# M7010X.net
KiCad netlist of a schematic drawn in EAGLE
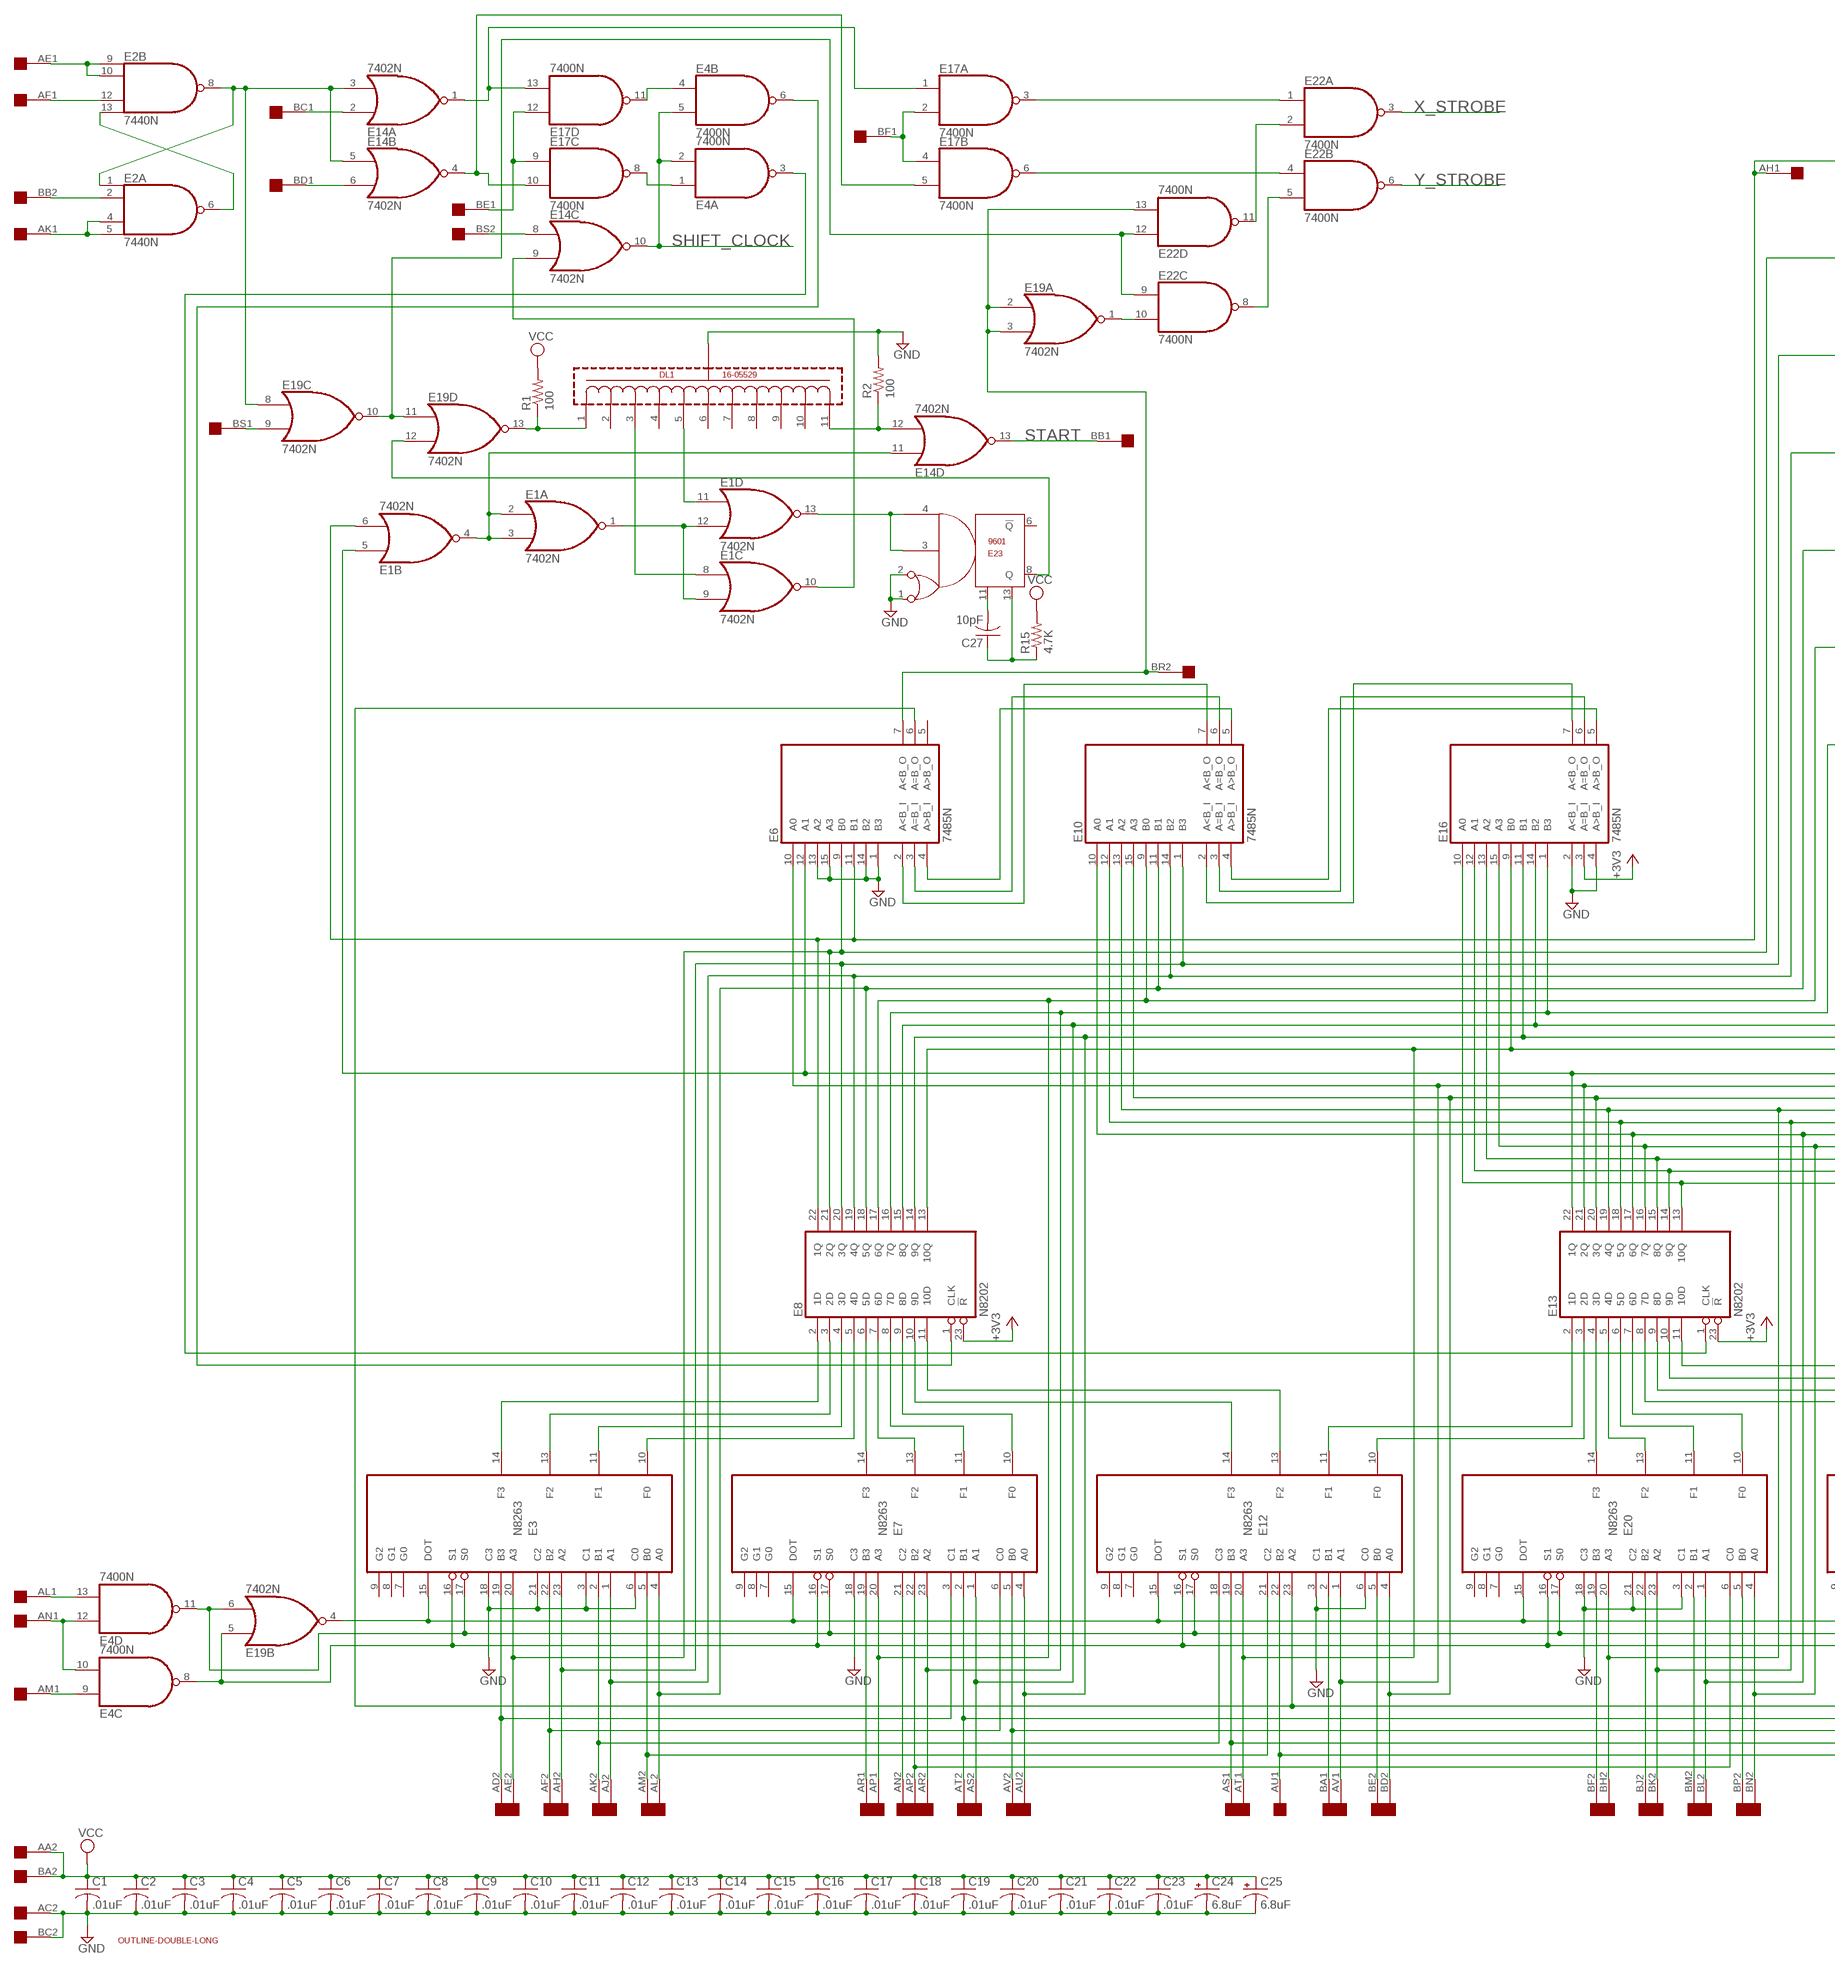
[diagram p0: schematic, sheet 1, part 1 of 2]
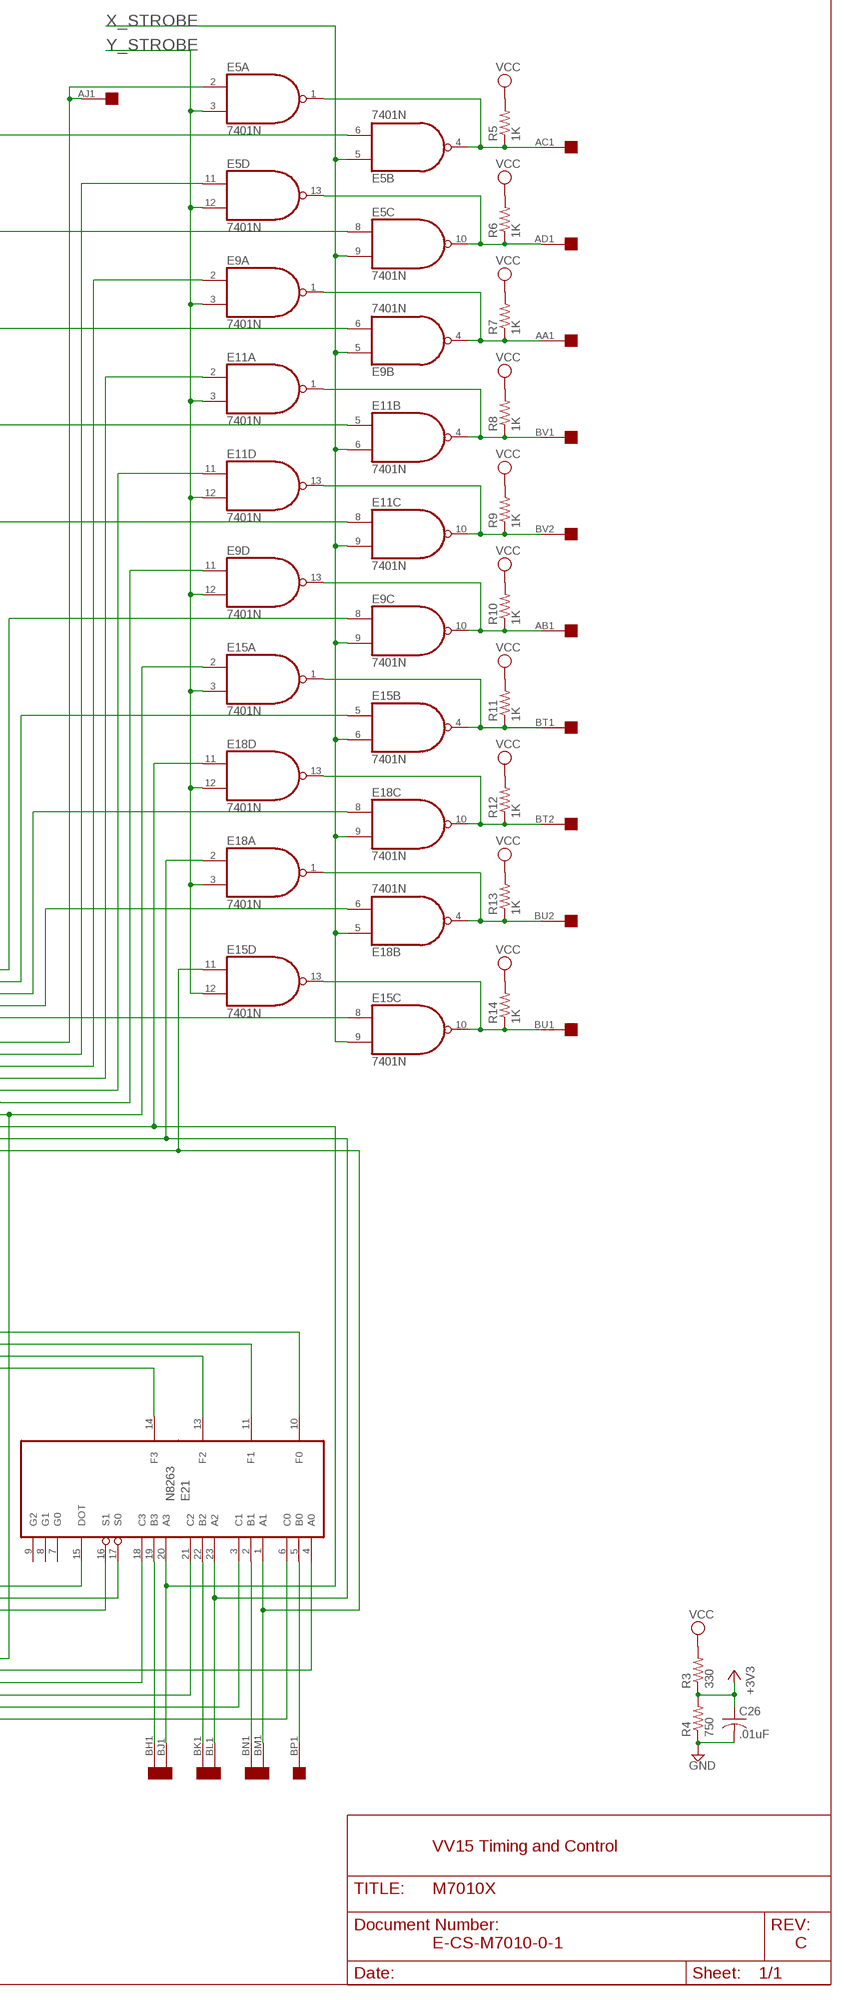
[diagram p1: schematic, sheet 1, part 2 of 2]

(export (version "E")
  (design (tool "Eeschema 10.0.6"))
  (components
    (comp (ref "C1")
      (value ".01uF")
      (footprint "eagle-import:C050-025X075")
      (libsource (lib "eagle-import") (part "C-US050-025X075"))
    )
    (comp (ref "C2")
      (value ".01uF")
      (footprint "eagle-import:C050-025X075")
      (libsource (lib "eagle-import") (part "C-US050-025X075"))
    )
    (comp (ref "C3")
      (value ".01uF")
      (footprint "eagle-import:C050-025X075")
      (libsource (lib "eagle-import") (part "C-US050-025X075"))
    )
    (comp (ref "C4")
      (value ".01uF")
      (footprint "eagle-import:C050-025X075")
      (libsource (lib "eagle-import") (part "C-US050-025X075"))
    )
    (comp (ref "C5")
      (value ".01uF")
      (footprint "eagle-import:C050-025X075")
      (libsource (lib "eagle-import") (part "C-US050-025X075"))
    )
    (comp (ref "C6")
      (value ".01uF")
      (footprint "eagle-import:C050-025X075")
      (libsource (lib "eagle-import") (part "C-US050-025X075"))
    )
    (comp (ref "C7")
      (value ".01uF")
      (footprint "eagle-import:C050-025X075")
      (libsource (lib "eagle-import") (part "C-US050-025X075"))
    )
    (comp (ref "C8")
      (value ".01uF")
      (footprint "eagle-import:C050-025X075")
      (libsource (lib "eagle-import") (part "C-US050-025X075"))
    )
    (comp (ref "C9")
      (value ".01uF")
      (footprint "eagle-import:C050-025X075")
      (libsource (lib "eagle-import") (part "C-US050-025X075"))
    )
    (comp (ref "C10")
      (value ".01uF")
      (footprint "eagle-import:C050-025X075")
      (libsource (lib "eagle-import") (part "C-US050-025X075"))
    )
    (comp (ref "C11")
      (value ".01uF")
      (footprint "eagle-import:C050-025X075")
      (libsource (lib "eagle-import") (part "C-US050-025X075"))
    )
    (comp (ref "C12")
      (value ".01uF")
      (footprint "eagle-import:C050-025X075")
      (libsource (lib "eagle-import") (part "C-US050-025X075"))
    )
    (comp (ref "C13")
      (value ".01uF")
      (footprint "eagle-import:C050-025X075")
      (libsource (lib "eagle-import") (part "C-US050-025X075"))
    )
    (comp (ref "C14")
      (value ".01uF")
      (footprint "eagle-import:C050-025X075")
      (libsource (lib "eagle-import") (part "C-US050-025X075"))
    )
    (comp (ref "C15")
      (value ".01uF")
      (footprint "eagle-import:C050-025X075")
      (libsource (lib "eagle-import") (part "C-US050-025X075"))
    )
    (comp (ref "C16")
      (value ".01uF")
      (footprint "eagle-import:C050-025X075")
      (libsource (lib "eagle-import") (part "C-US050-025X075"))
    )
    (comp (ref "C17")
      (value ".01uF")
      (footprint "eagle-import:C050-025X075")
      (libsource (lib "eagle-import") (part "C-US050-025X075"))
    )
    (comp (ref "C18")
      (value ".01uF")
      (footprint "eagle-import:C050-025X075")
      (libsource (lib "eagle-import") (part "C-US050-025X075"))
    )
    (comp (ref "C19")
      (value ".01uF")
      (footprint "eagle-import:C050-025X075")
      (libsource (lib "eagle-import") (part "C-US050-025X075"))
    )
    (comp (ref "C20")
      (value ".01uF")
      (footprint "eagle-import:C050-025X075")
      (libsource (lib "eagle-import") (part "C-US050-025X075"))
    )
    (comp (ref "C21")
      (value ".01uF")
      (footprint "eagle-import:C050-025X075")
      (libsource (lib "eagle-import") (part "C-US050-025X075"))
    )
    (comp (ref "C22")
      (value ".01uF")
      (footprint "eagle-import:C050-025X075")
      (libsource (lib "eagle-import") (part "C-US050-025X075"))
    )
    (comp (ref "C23")
      (value ".01uF")
      (footprint "eagle-import:C050-025X075")
      (libsource (lib "eagle-import") (part "C-US050-025X075"))
    )
    (comp (ref "C24")
      (value "6.8uF")
      (footprint "eagle-import:E12-8")
      (libsource (lib "eagle-import") (part "CPOL-USE20-8AXIAL"))
    )
    (comp (ref "C25")
      (value "6.8uF")
      (footprint "eagle-import:E12-8")
      (libsource (lib "eagle-import") (part "CPOL-USE20-8AXIAL"))
    )
    (comp (ref "C26")
      (value ".01uF")
      (footprint "eagle-import:C050-025X075")
      (libsource (lib "eagle-import") (part "C-US050-025X075"))
    )
    (comp (ref "C27")
      (value "10pF")
      (footprint "eagle-import:C050-025X075")
      (libsource (lib "eagle-import") (part "C-US050-025X075"))
    )
    (comp (ref "DL1")
      (value "16-05529")
      (footprint "eagle-import:16-05529")
      (libsource (lib "eagle-import") (part "16-05529"))
    )
    (comp (ref "E1")
      (value "7402N")
      (footprint "eagle-import:DIL14")
      (libsource (lib "eagle-import") (part "7402N"))
    )
    (comp (ref "E2")
      (value "7440N")
      (footprint "eagle-import:DIL14")
      (libsource (lib "eagle-import") (part "7420N"))
    )
    (comp (ref "E3")
      (value "N8263")
      (footprint "eagle-import:DIL24")
      (libsource (lib "eagle-import") (part "N8263"))
    )
    (comp (ref "E4")
      (value "7400N")
      (footprint "eagle-import:DIL14")
      (libsource (lib "eagle-import") (part "7400N"))
    )
    (comp (ref "E5")
      (value "7401N")
      (footprint "eagle-import:DIL14")
      (libsource (lib "eagle-import") (part "7401NLS"))
    )
    (comp (ref "E6")
      (value "7485N")
      (footprint "eagle-import:DIL16")
      (libsource (lib "eagle-import") (part "7485N"))
    )
    (comp (ref "E7")
      (value "N8263")
      (footprint "eagle-import:DIL24")
      (libsource (lib "eagle-import") (part "N8263"))
    )
    (comp (ref "E8")
      (value "N8202")
      (footprint "eagle-import:DIL24")
      (libsource (lib "eagle-import") (part "N8202"))
    )
    (comp (ref "E9")
      (value "7401N")
      (footprint "eagle-import:DIL14")
      (libsource (lib "eagle-import") (part "7401NLS"))
    )
    (comp (ref "E10")
      (value "7485N")
      (footprint "eagle-import:DIL16")
      (libsource (lib "eagle-import") (part "7485N"))
    )
    (comp (ref "E11")
      (value "7401N")
      (footprint "eagle-import:DIL14")
      (libsource (lib "eagle-import") (part "7401NLS"))
    )
    (comp (ref "E12")
      (value "N8263")
      (footprint "eagle-import:DIL24")
      (libsource (lib "eagle-import") (part "N8263"))
    )
    (comp (ref "E13")
      (value "N8202")
      (footprint "eagle-import:DIL24")
      (libsource (lib "eagle-import") (part "N8202"))
    )
    (comp (ref "E14")
      (value "7402N")
      (footprint "eagle-import:DIL14")
      (libsource (lib "eagle-import") (part "7402N"))
    )
    (comp (ref "E15")
      (value "7401N")
      (footprint "eagle-import:DIL14")
      (libsource (lib "eagle-import") (part "7401NLS"))
    )
    (comp (ref "E16")
      (value "7485N")
      (footprint "eagle-import:DIL16")
      (libsource (lib "eagle-import") (part "7485N"))
    )
    (comp (ref "E17")
      (value "7400N")
      (footprint "eagle-import:DIL14")
      (libsource (lib "eagle-import") (part "7400N"))
    )
    (comp (ref "E18")
      (value "7401N")
      (footprint "eagle-import:DIL14")
      (libsource (lib "eagle-import") (part "7401NLS"))
    )
    (comp (ref "E19")
      (value "7402N")
      (footprint "eagle-import:DIL14")
      (libsource (lib "eagle-import") (part "7402N"))
    )
    (comp (ref "E20")
      (value "N8263")
      (footprint "eagle-import:DIL24")
      (libsource (lib "eagle-import") (part "N8263"))
    )
    (comp (ref "E21")
      (value "N8263")
      (footprint "eagle-import:DIL24")
      (libsource (lib "eagle-import") (part "N8263"))
    )
    (comp (ref "E22")
      (value "7400N")
      (footprint "eagle-import:DIL14")
      (libsource (lib "eagle-import") (part "7400N"))
    )
    (comp (ref "E23")
      (value "9601")
      (footprint "eagle-import:DIL14")
      (libsource (lib "eagle-import") (part "9601"))
    )
    (comp (ref "R1")
      (value "100")
      (footprint "eagle-import:0207_10")
      (libsource (lib "eagle-import") (part "R-US_0207/10"))
    )
    (comp (ref "R2")
      (value "100")
      (footprint "eagle-import:0207_10")
      (libsource (lib "eagle-import") (part "R-US_0207/10"))
    )
    (comp (ref "R3")
      (value "330")
      (footprint "eagle-import:0207_10")
      (libsource (lib "eagle-import") (part "R-US_0207/10"))
    )
    (comp (ref "R4")
      (value "750")
      (footprint "eagle-import:0207_10")
      (libsource (lib "eagle-import") (part "R-US_0207/10"))
    )
    (comp (ref "R5")
      (value "1K")
      (footprint "eagle-import:0207_10")
      (libsource (lib "eagle-import") (part "R-US_0207/10"))
    )
    (comp (ref "R6")
      (value "1K")
      (footprint "eagle-import:0207_10")
      (libsource (lib "eagle-import") (part "R-US_0207/10"))
    )
    (comp (ref "R7")
      (value "1K")
      (footprint "eagle-import:0207_10")
      (libsource (lib "eagle-import") (part "R-US_0207/10"))
    )
    (comp (ref "R8")
      (value "1K")
      (footprint "eagle-import:0207_10")
      (libsource (lib "eagle-import") (part "R-US_0207/10"))
    )
    (comp (ref "R9")
      (value "1K")
      (footprint "eagle-import:0207_10")
      (libsource (lib "eagle-import") (part "R-US_0207/10"))
    )
    (comp (ref "R10")
      (value "1K")
      (footprint "eagle-import:0207_10")
      (libsource (lib "eagle-import") (part "R-US_0207/10"))
    )
    (comp (ref "R11")
      (value "1K")
      (footprint "eagle-import:0207_10")
      (libsource (lib "eagle-import") (part "R-US_0207/10"))
    )
    (comp (ref "R12")
      (value "1K")
      (footprint "eagle-import:0207_10")
      (libsource (lib "eagle-import") (part "R-US_0207/10"))
    )
    (comp (ref "R13")
      (value "1K")
      (footprint "eagle-import:0207_10")
      (libsource (lib "eagle-import") (part "R-US_0207/10"))
    )
    (comp (ref "R14")
      (value "1K")
      (footprint "eagle-import:0207_10")
      (libsource (lib "eagle-import") (part "R-US_0207/10"))
    )
    (comp (ref "R15")
      (value "4.7K")
      (footprint "eagle-import:0207_10")
      (libsource (lib "eagle-import") (part "R-US_0207/10"))
    )
    (comp (ref "U$1")
      (value "OUTLINE-DOUBLE-LONG")
      (footprint "eagle-import:DOUBLE-LONG")
      (libsource (lib "eagle-import") (part "OUTLINE-DOUBLE-LONG"))
    )
    (comp (ref "U$3")
      (value "DOUBLE")
      (footprint "eagle-import:EDGE-CON4")
      (libsource (lib "eagle-import") (part "DOUBLE"))
    )
  )
  (nets
    (net (code "1") (name "+3V3") (class "Default")
      (node (ref "C26") (pin "1") (pinfunction "1_1") (pintype "passive"))
      (node (ref "E13") (pin "23") (pinfunction "~{R}_23") (pintype "input"))
      (node (ref "E16") (pin "3") (pinfunction "A=B_I_3") (pintype "input"))
      (node (ref "E8") (pin "23") (pinfunction "~{R}_23") (pintype "input"))
      (node (ref "R3") (pin "1") (pinfunction "1_1") (pintype "passive"))
      (node (ref "R4") (pin "2") (pinfunction "2_2") (pintype "passive"))
    )
    (net (code "2") (name "/SHIFT_CLOCK") (class "Default")
      (node (ref "E14") (pin "10") (pinfunction "O_10") (pintype "output"))
      (node (ref "E4") (pin "2") (pinfunction "I1_2") (pintype "input"))
      (node (ref "E4") (pin "5") (pinfunction "I1_5") (pintype "input"))
    )
    (net (code "3") (name "/START") (class "Default")
      (node (ref "E14") (pin "13") (pinfunction "O_13") (pintype "output"))
      (node (ref "U$3") (pin "BB1") (pinfunction "1_BB1") (pintype "bidirectional"))
    )
    (net (code "4") (name "/X_STROBE") (class "Default")
      (node (ref "E11") (pin "6") (pinfunction "I1_6") (pintype "input"))
      (node (ref "E11") (pin "9") (pinfunction "I1_9") (pintype "input"))
      (node (ref "E15") (pin "6") (pinfunction "I1_6") (pintype "input"))
      (node (ref "E15") (pin "9") (pinfunction "I1_9") (pintype "input"))
      (node (ref "E18") (pin "5") (pinfunction "I0_5") (pintype "input"))
      (node (ref "E18") (pin "9") (pinfunction "I1_9") (pintype "input"))
      (node (ref "E22") (pin "3") (pinfunction "O_3") (pintype "output"))
      (node (ref "E5") (pin "5") (pinfunction "I0_5") (pintype "input"))
      (node (ref "E5") (pin "9") (pinfunction "I1_9") (pintype "input"))
      (node (ref "E9") (pin "5") (pinfunction "I0_5") (pintype "input"))
      (node (ref "E9") (pin "9") (pinfunction "I1_9") (pintype "input"))
    )
    (net (code "5") (name "/Y_STROBE") (class "Default")
      (node (ref "E11") (pin "12") (pinfunction "I1_12") (pintype "input"))
      (node (ref "E11") (pin "3") (pinfunction "I1_3") (pintype "input"))
      (node (ref "E15") (pin "12") (pinfunction "I1_12") (pintype "input"))
      (node (ref "E15") (pin "3") (pinfunction "I1_3") (pintype "input"))
      (node (ref "E18") (pin "12") (pinfunction "I1_12") (pintype "input"))
      (node (ref "E18") (pin "3") (pinfunction "I1_3") (pintype "input"))
      (node (ref "E22") (pin "6") (pinfunction "O_6") (pintype "output"))
      (node (ref "E5") (pin "12") (pinfunction "I1_12") (pintype "input"))
      (node (ref "E5") (pin "3") (pinfunction "I1_3") (pintype "input"))
      (node (ref "E9") (pin "12") (pinfunction "I1_12") (pintype "input"))
      (node (ref "E9") (pin "3") (pinfunction "I1_3") (pintype "input"))
    )
    (net (code "6") (name "GND") (class "Default")
      (node (ref "C1") (pin "2") (pinfunction "2_2") (pintype "passive"))
      (node (ref "C10") (pin "2") (pinfunction "2_2") (pintype "passive"))
      (node (ref "C11") (pin "2") (pinfunction "2_2") (pintype "passive"))
      (node (ref "C12") (pin "2") (pinfunction "2_2") (pintype "passive"))
      (node (ref "C13") (pin "2") (pinfunction "2_2") (pintype "passive"))
      (node (ref "C14") (pin "2") (pinfunction "2_2") (pintype "passive"))
      (node (ref "C15") (pin "2") (pinfunction "2_2") (pintype "passive"))
      (node (ref "C16") (pin "2") (pinfunction "2_2") (pintype "passive"))
      (node (ref "C17") (pin "2") (pinfunction "2_2") (pintype "passive"))
      (node (ref "C18") (pin "2") (pinfunction "2_2") (pintype "passive"))
      (node (ref "C19") (pin "2") (pinfunction "2_2") (pintype "passive"))
      (node (ref "C2") (pin "2") (pinfunction "2_2") (pintype "passive"))
      (node (ref "C20") (pin "2") (pinfunction "2_2") (pintype "passive"))
      (node (ref "C21") (pin "2") (pinfunction "2_2") (pintype "passive"))
      (node (ref "C22") (pin "2") (pinfunction "2_2") (pintype "passive"))
      (node (ref "C23") (pin "2") (pinfunction "2_2") (pintype "passive"))
      (node (ref "C24") (pin "-") (pinfunction "-_-") (pintype "passive"))
      (node (ref "C25") (pin "-") (pinfunction "-_-") (pintype "passive"))
      (node (ref "C26") (pin "2") (pinfunction "2_2") (pintype "passive"))
      (node (ref "C3") (pin "2") (pinfunction "2_2") (pintype "passive"))
      (node (ref "C4") (pin "2") (pinfunction "2_2") (pintype "passive"))
      (node (ref "C5") (pin "2") (pinfunction "2_2") (pintype "passive"))
      (node (ref "C6") (pin "2") (pinfunction "2_2") (pintype "passive"))
      (node (ref "C7") (pin "2") (pinfunction "2_2") (pintype "passive"))
      (node (ref "C8") (pin "2") (pinfunction "2_2") (pintype "passive"))
      (node (ref "C9") (pin "2") (pinfunction "2_2") (pintype "passive"))
      (node (ref "DL1") (pin "12") (pinfunction "GND_12") (pintype "passive"))
      (node (ref "E12") (pin "3") (pinfunction "C1_3") (pintype "input"))
      (node (ref "E12") (pin "6") (pinfunction "C0_6") (pintype "input"))
      (node (ref "E16") (pin "2") (pinfunction "A<B_I_2") (pintype "input"))
      (node (ref "E16") (pin "4") (pinfunction "A>B_I_4") (pintype "input"))
      (node (ref "E20") (pin "18") (pinfunction "C3_18") (pintype "input"))
      (node (ref "E20") (pin "21") (pinfunction "C2_21") (pintype "input"))
      (node (ref "E20") (pin "3") (pinfunction "C1_3") (pintype "input"))
      (node (ref "E23") (pin "1") (pinfunction "P$1_1") (pintype "input"))
      (node (ref "E23") (pin "2") (pinfunction "P$2_2") (pintype "input"))
      (node (ref "E3") (pin "18") (pinfunction "C3_18") (pintype "input"))
      (node (ref "E3") (pin "21") (pinfunction "C2_21") (pintype "input"))
      (node (ref "E3") (pin "3") (pinfunction "C1_3") (pintype "input"))
      (node (ref "E3") (pin "6") (pinfunction "C0_6") (pintype "input"))
      (node (ref "E6") (pin "1") (pinfunction "B3_1") (pintype "input"))
      (node (ref "E6") (pin "13") (pinfunction "A2_13") (pintype "input"))
      (node (ref "E6") (pin "14") (pinfunction "B2_14") (pintype "input"))
      (node (ref "E6") (pin "15") (pinfunction "A3_15") (pintype "input"))
      (node (ref "E7") (pin "18") (pinfunction "C3_18") (pintype "input"))
      (node (ref "R2") (pin "2") (pinfunction "2_2") (pintype "passive"))
      (node (ref "R4") (pin "1") (pinfunction "1_1") (pintype "passive"))
      (node (ref "U$3") (pin "AC2") (pinfunction "1_AC2") (pintype "bidirectional"))
      (node (ref "U$3") (pin "BC2") (pinfunction "1_BC2") (pintype "bidirectional"))
    )
    (net (code "7") (name "Net-(DL1-0)") (class "Default")
      (node (ref "DL1") (pin "1") (pinfunction "0_1") (pintype "passive"))
      (node (ref "E19") (pin "13") (pinfunction "O_13") (pintype "output"))
      (node (ref "R1") (pin "1") (pinfunction "1_1") (pintype "passive"))
    )
    (net (code "8") (name "Net-(DL1-10)") (class "Default")
      (node (ref "DL1") (pin "3") (pinfunction "10_3") (pintype "passive"))
      (node (ref "E1") (pin "8") (pinfunction "I0_8") (pintype "input"))
    )
    (net (code "9") (name "Net-(DL1-20)") (class "Default")
      (node (ref "DL1") (pin "5") (pinfunction "20_5") (pintype "passive"))
      (node (ref "E1") (pin "11") (pinfunction "I0_11") (pintype "input"))
    )
    (net (code "10") (name "Net-(DL1-50)") (class "Default")
      (node (ref "DL1") (pin "11") (pinfunction "50_11") (pintype "passive"))
      (node (ref "E14") (pin "12") (pinfunction "I1_12") (pintype "input"))
      (node (ref "R2") (pin "1") (pinfunction "1_1") (pintype "passive"))
    )
    (net (code "11") (name "Net-(E1A-O)") (class "Default")
      (node (ref "E1") (pin "1") (pinfunction "O_1") (pintype "output"))
      (node (ref "E1") (pin "12") (pinfunction "I1_12") (pintype "input"))
      (node (ref "E1") (pin "9") (pinfunction "I1_9") (pintype "input"))
    )
    (net (code "12") (name "Net-(E1B-I1)") (class "Default")
      (node (ref "E1") (pin "6") (pinfunction "I1_6") (pintype "input"))
      (node (ref "E5") (pin "6") (pinfunction "I1_6") (pintype "input"))
      (node (ref "E6") (pin "11") (pinfunction "B1_11") (pintype "input"))
      (node (ref "E8") (pin "22") (pinfunction "1Q_22") (pintype "tri_state"))
      (node (ref "U$3") (pin "AH1") (pinfunction "1_AH1") (pintype "bidirectional"))
    )
    (net (code "13") (name "Net-(E1D-O)") (class "Default")
      (node (ref "E1") (pin "13") (pinfunction "O_13") (pintype "output"))
      (node (ref "E23") (pin "3") (pinfunction "P$3_3") (pintype "input"))
      (node (ref "E23") (pin "4") (pinfunction "P$4_4") (pintype "input"))
    )
    (net (code "14") (name "Net-(E2C-I1)") (class "Default")
      (node (ref "E2") (pin "2") (pinfunction "I1_2") (pintype "input"))
      (node (ref "U$3") (pin "BB2") (pinfunction "1_BB2") (pintype "bidirectional"))
    )
    (net (code "15") (name "Net-(E2C-I2)") (class "Default")
      (node (ref "E2") (pin "4") (pinfunction "I2_4") (pintype "input"))
      (node (ref "E2") (pin "5") (pinfunction "I3_5") (pintype "input"))
      (node (ref "U$3") (pin "AK1") (pinfunction "1_AK1") (pintype "bidirectional"))
    )
    (net (code "16") (name "Net-(E2C-O)") (class "Default")
      (node (ref "E2") (pin "13") (pinfunction "I3_13") (pintype "input"))
      (node (ref "E2") (pin "6") (pinfunction "O_6") (pintype "output"))
    )
    (net (code "17") (name "Net-(E2D-I0)") (class "Default")
      (node (ref "E2") (pin "10") (pinfunction "I1_10") (pintype "input"))
      (node (ref "E2") (pin "9") (pinfunction "I0_9") (pintype "input"))
      (node (ref "U$3") (pin "AE1") (pinfunction "1_AE1") (pintype "bidirectional"))
    )
    (net (code "18") (name "Net-(E2D-I2)") (class "Default")
      (node (ref "E2") (pin "12") (pinfunction "I2_12") (pintype "input"))
      (node (ref "U$3") (pin "AF1") (pinfunction "1_AF1") (pintype "bidirectional"))
    )
    (net (code "19") (name "Net-(E3A-A3)") (class "Default")
      (node (ref "E3") (pin "20") (pinfunction "A3_20") (pintype "input"))
      (node (ref "E5") (pin "8") (pinfunction "I0_8") (pintype "input"))
      (node (ref "E6") (pin "9") (pinfunction "B0_9") (pintype "input"))
      (node (ref "E8") (pin "21") (pinfunction "2Q_21") (pintype "tri_state"))
      (node (ref "U$3") (pin "AE2") (pinfunction "1_AE2") (pintype "bidirectional"))
    )
    (net (code "20") (name "Net-(E3A-B2)") (class "Default")
      (node (ref "E3") (pin "22") (pinfunction "B2_22") (pintype "input"))
      (node (ref "E7") (pin "6") (pinfunction "C0_6") (pintype "input"))
      (node (ref "U$3") (pin "AF2") (pinfunction "1_AF2") (pintype "bidirectional"))
    )
    (net (code "21") (name "Net-(E3A-B3)") (class "Default")
      (node (ref "E3") (pin "19") (pinfunction "B3_19") (pintype "input"))
      (node (ref "E7") (pin "3") (pinfunction "C1_3") (pintype "input"))
      (node (ref "U$3") (pin "AD2") (pinfunction "1_AD2") (pintype "bidirectional"))
    )
    (net (code "22") (name "Net-(E3A-F0)") (class "Default")
      (node (ref "E3") (pin "10") (pinfunction "F0_10") (pintype "output"))
      (node (ref "E8") (pin "5") (pinfunction "4D_5") (pintype "input"))
    )
    (net (code "23") (name "Net-(E3A-F1)") (class "Default")
      (node (ref "E3") (pin "11") (pinfunction "F1_11") (pintype "output"))
      (node (ref "E8") (pin "4") (pinfunction "3D_4") (pintype "input"))
    )
    (net (code "24") (name "Net-(E3A-F2)") (class "Default")
      (node (ref "E3") (pin "13") (pinfunction "F2_13") (pintype "output"))
      (node (ref "E8") (pin "3") (pinfunction "2D_3") (pintype "input"))
    )
    (net (code "25") (name "Net-(E3A-F3)") (class "Default")
      (node (ref "E3") (pin "14") (pinfunction "F3_14") (pintype "output"))
      (node (ref "E8") (pin "2") (pinfunction "1D_2") (pintype "input"))
    )
    (net (code "26") (name "Net-(E4B-O)") (class "Default")
      (node (ref "E4") (pin "6") (pinfunction "O_6") (pintype "output"))
      (node (ref "E8") (pin "1") (pinfunction "CLK_1") (pintype "input"))
    )
    (net (code "27") (name "Net-(E4C-I0)") (class "Default")
      (node (ref "E4") (pin "9") (pinfunction "I0_9") (pintype "input"))
      (node (ref "U$3") (pin "AM1") (pinfunction "1_AM1") (pintype "bidirectional"))
    )
    (net (code "28") (name "Net-(E4C-I1)") (class "Default")
      (node (ref "E4") (pin "10") (pinfunction "I1_10") (pintype "input"))
      (node (ref "E4") (pin "12") (pinfunction "I0_12") (pintype "input"))
      (node (ref "U$3") (pin "AN1") (pinfunction "1_AN1") (pintype "bidirectional"))
    )
    (net (code "29") (name "Net-(E4D-I1)") (class "Default")
      (node (ref "E4") (pin "13") (pinfunction "I1_13") (pintype "input"))
      (node (ref "U$3") (pin "AL1") (pinfunction "1_AL1") (pintype "bidirectional"))
    )
    (net (code "30") (name "Net-(E5A-O)") (class "Default")
      (node (ref "E5") (pin "1") (pinfunction "O_1") (pintype "open_collector"))
      (node (ref "E5") (pin "4") (pinfunction "O_4") (pintype "open_collector"))
      (node (ref "R5") (pin "1") (pinfunction "1_1") (pintype "passive"))
      (node (ref "U$3") (pin "AC1") (pinfunction "1_AC1") (pintype "bidirectional"))
    )
    (net (code "31") (name "Net-(E5C-O)") (class "Default")
      (node (ref "E5") (pin "10") (pinfunction "O_10") (pintype "open_collector"))
      (node (ref "E5") (pin "13") (pinfunction "O_13") (pintype "open_collector"))
      (node (ref "R6") (pin "1") (pinfunction "1_1") (pintype "passive"))
      (node (ref "U$3") (pin "AD1") (pinfunction "1_AD1") (pintype "bidirectional"))
    )
    (net (code "32") (name "Net-(E7A-B3)") (class "Default")
      (node (ref "E7") (pin "19") (pinfunction "B3_19") (pintype "input"))
      (node (ref "U$3") (pin "AR1") (pinfunction "1_AR1") (pintype "bidirectional"))
    )
    (net (code "33") (name "Net-(E7A-C2)") (class "Default")
      (node (ref "E7") (pin "21") (pinfunction "C2_21") (pintype "input"))
      (node (ref "U$3") (pin "AN2") (pinfunction "1_AN2") (pintype "bidirectional"))
    )
    (net (code "34") (name "Net-(E7A-F0)") (class "Default")
      (node (ref "E7") (pin "10") (pinfunction "F0_10") (pintype "output"))
      (node (ref "E8") (pin "9") (pinfunction "8D_9") (pintype "input"))
    )
    (net (code "35") (name "Net-(E7A-F1)") (class "Default")
      (node (ref "E7") (pin "11") (pinfunction "F1_11") (pintype "output"))
      (node (ref "E8") (pin "8") (pinfunction "7D_8") (pintype "input"))
    )
    (net (code "36") (name "Net-(E7A-F2)") (class "Default")
      (node (ref "E7") (pin "13") (pinfunction "F2_13") (pintype "output"))
      (node (ref "E8") (pin "7") (pinfunction "6D_7") (pintype "input"))
    )
    (net (code "37") (name "Net-(E7A-F3)") (class "Default")
      (node (ref "E7") (pin "14") (pinfunction "F3_14") (pintype "output"))
      (node (ref "E8") (pin "6") (pinfunction "5D_6") (pintype "input"))
    )
    (net (code "38") (name "Net-(E9A-O)") (class "Default")
      (node (ref "E9") (pin "1") (pinfunction "O_1") (pintype "open_collector"))
      (node (ref "E9") (pin "4") (pinfunction "O_4") (pintype "open_collector"))
      (node (ref "R7") (pin "1") (pinfunction "1_1") (pintype "passive"))
      (node (ref "U$3") (pin "AA1") (pinfunction "1_AA1") (pintype "bidirectional"))
    )
    (net (code "39") (name "Net-(E9C-O)") (class "Default")
      (node (ref "E9") (pin "10") (pinfunction "O_10") (pintype "open_collector"))
      (node (ref "E9") (pin "13") (pinfunction "O_13") (pintype "open_collector"))
      (node (ref "R10") (pin "1") (pinfunction "1_1") (pintype "passive"))
      (node (ref "U$3") (pin "AB1") (pinfunction "1_AB1") (pintype "bidirectional"))
    )
    (net (code "40") (name "Net-(E10A-A0)") (class "Default")
      (node (ref "E10") (pin "10") (pinfunction "A0_10") (pintype "input"))
      (node (ref "E13") (pin "17") (pinfunction "6Q_17") (pintype "tri_state"))
      (node (ref "E20") (pin "1") (pinfunction "A1_1") (pintype "input"))
      (node (ref "E9") (pin "11") (pinfunction "I0_11") (pintype "input"))
      (node (ref "U$3") (pin "BL2") (pinfunction "1_BL2") (pintype "bidirectional"))
    )
    (net (code "41") (name "Net-(E10A-A1)") (class "Default")
      (node (ref "E10") (pin "12") (pinfunction "A1_12") (pintype "input"))
      (node (ref "E11") (pin "11") (pinfunction "I0_11") (pintype "input"))
      (node (ref "E13") (pin "18") (pinfunction "5Q_18") (pintype "tri_state"))
      (node (ref "E20") (pin "23") (pinfunction "A2_23") (pintype "input"))
      (node (ref "U$3") (pin "BK2") (pinfunction "1_BK2") (pintype "bidirectional"))
    )
    (net (code "42") (name "Net-(E10A-A2)") (class "Default")
      (node (ref "E10") (pin "13") (pinfunction "A2_13") (pintype "input"))
      (node (ref "E11") (pin "2") (pinfunction "I0_2") (pintype "input"))
      (node (ref "E13") (pin "19") (pinfunction "4Q_19") (pintype "tri_state"))
      (node (ref "E20") (pin "20") (pinfunction "A3_20") (pintype "input"))
      (node (ref "U$3") (pin "BH2") (pinfunction "1_BH2") (pintype "bidirectional"))
    )
    (net (code "43") (name "Net-(E10A-A3)") (class "Default")
      (node (ref "E10") (pin "15") (pinfunction "A3_15") (pintype "input"))
      (node (ref "E12") (pin "4") (pinfunction "A0_4") (pintype "input"))
      (node (ref "E13") (pin "20") (pinfunction "3Q_20") (pintype "tri_state"))
      (node (ref "E9") (pin "2") (pinfunction "I0_2") (pintype "input"))
      (node (ref "U$3") (pin "BD2") (pinfunction "1_BD2") (pintype "bidirectional"))
    )
    (net (code "44") (name "Net-(E10A-A<B_I)") (class "Default")
      (node (ref "E10") (pin "2") (pinfunction "A<B_I_2") (pintype "input"))
      (node (ref "E16") (pin "7") (pinfunction "A<B_O_7") (pintype "output"))
    )
    (net (code "45") (name "Net-(E10A-A<B_O)") (class "Default")
      (node (ref "E10") (pin "7") (pinfunction "A<B_O_7") (pintype "output"))
      (node (ref "E6") (pin "2") (pinfunction "A<B_I_2") (pintype "input"))
    )
    (net (code "46") (name "Net-(E10A-A=B_I)") (class "Default")
      (node (ref "E10") (pin "3") (pinfunction "A=B_I_3") (pintype "input"))
      (node (ref "E16") (pin "6") (pinfunction "A=B_O_6") (pintype "output"))
    )
    (net (code "47") (name "Net-(E10A-A=B_O)") (class "Default")
      (node (ref "E10") (pin "6") (pinfunction "A=B_O_6") (pintype "output"))
      (node (ref "E6") (pin "3") (pinfunction "A=B_I_3") (pintype "input"))
    )
    (net (code "48") (name "Net-(E10A-A>B_I)") (class "Default")
      (node (ref "E10") (pin "4") (pinfunction "A>B_I_4") (pintype "input"))
      (node (ref "E16") (pin "5") (pinfunction "A>B_O_5") (pintype "output"))
    )
    (net (code "49") (name "Net-(E10A-A>B_O)") (class "Default")
      (node (ref "E10") (pin "5") (pinfunction "A>B_O_5") (pintype "output"))
      (node (ref "E6") (pin "4") (pinfunction "A>B_I_4") (pintype "input"))
    )
    (net (code "50") (name "Net-(E10A-B0)") (class "Default")
      (node (ref "E10") (pin "9") (pinfunction "B0_9") (pintype "input"))
      (node (ref "E7") (pin "20") (pinfunction "A3_20") (pintype "input"))
      (node (ref "E8") (pin "17") (pinfunction "6Q_17") (pintype "tri_state"))
      (node (ref "E9") (pin "8") (pinfunction "I0_8") (pintype "input"))
      (node (ref "U$3") (pin "AP1") (pinfunction "1_AP1") (pintype "bidirectional"))
    )
    (net (code "51") (name "Net-(E10A-B1)") (class "Default")
      (node (ref "E10") (pin "11") (pinfunction "B1_11") (pintype "input"))
      (node (ref "E11") (pin "8") (pinfunction "I0_8") (pintype "input"))
      (node (ref "E3") (pin "4") (pinfunction "A0_4") (pintype "input"))
      (node (ref "E8") (pin "18") (pinfunction "5Q_18") (pintype "tri_state"))
      (node (ref "U$3") (pin "AL2") (pinfunction "1_AL2") (pintype "bidirectional"))
    )
    (net (code "52") (name "Net-(E10A-B2)") (class "Default")
      (node (ref "E10") (pin "14") (pinfunction "B2_14") (pintype "input"))
      (node (ref "E11") (pin "5") (pinfunction "I0_5") (pintype "input"))
      (node (ref "E3") (pin "1") (pinfunction "A1_1") (pintype "input"))
      (node (ref "E8") (pin "19") (pinfunction "4Q_19") (pintype "tri_state"))
      (node (ref "U$3") (pin "AJ2") (pinfunction "1_AJ2") (pintype "bidirectional"))
    )
    (net (code "53") (name "Net-(E10A-B3)") (class "Default")
      (node (ref "E10") (pin "1") (pinfunction "B3_1") (pintype "input"))
      (node (ref "E3") (pin "23") (pinfunction "A2_23") (pintype "input"))
      (node (ref "E8") (pin "20") (pinfunction "3Q_20") (pintype "tri_state"))
      (node (ref "E9") (pin "6") (pinfunction "I1_6") (pintype "input"))
      (node (ref "U$3") (pin "AH2") (pinfunction "1_AH2") (pintype "bidirectional"))
    )
    (net (code "54") (name "Net-(E11A-O)") (class "Default")
      (node (ref "E11") (pin "1") (pinfunction "O_1") (pintype "open_collector"))
      (node (ref "E11") (pin "4") (pinfunction "O_4") (pintype "open_collector"))
      (node (ref "R8") (pin "1") (pinfunction "1_1") (pintype "passive"))
      (node (ref "U$3") (pin "BV1") (pinfunction "1_BV1") (pintype "bidirectional"))
    )
    (net (code "55") (name "Net-(E11C-O)") (class "Default")
      (node (ref "E11") (pin "10") (pinfunction "O_10") (pintype "open_collector"))
      (node (ref "E11") (pin "13") (pinfunction "O_13") (pintype "open_collector"))
      (node (ref "R9") (pin "1") (pinfunction "1_1") (pintype "passive"))
      (node (ref "U$3") (pin "BV2") (pinfunction "1_BV2") (pintype "bidirectional"))
    )
    (net (code "56") (name "Net-(E12A-A1)") (class "Default")
      (node (ref "E12") (pin "1") (pinfunction "A1_1") (pintype "input"))
      (node (ref "E13") (pin "21") (pinfunction "2Q_21") (pintype "tri_state"))
      (node (ref "E5") (pin "11") (pinfunction "I0_11") (pintype "input"))
      (node (ref "E6") (pin "10") (pinfunction "A0_10") (pintype "input"))
      (node (ref "U$3") (pin "AV1") (pinfunction "1_AV1") (pintype "bidirectional"))
    )
    (net (code "57") (name "Net-(E12A-A2)") (class "Default")
      (node (ref "E12") (pin "23") (pinfunction "A2_23") (pintype "input"))
      (node (ref "E21") (pin "4") (pinfunction "A0_4") (pintype "input"))
      (node (ref "E6") (pin "6") (pinfunction "A=B_O_6") (pintype "output"))
    )
    (net (code "58") (name "Net-(E12A-A3)") (class "Default")
      (node (ref "E12") (pin "20") (pinfunction "A3_20") (pintype "input"))
      (node (ref "E15") (pin "8") (pinfunction "I0_8") (pintype "input"))
      (node (ref "E16") (pin "9") (pinfunction "B0_9") (pintype "input"))
      (node (ref "E8") (pin "13") (pinfunction "10Q_13") (pintype "tri_state"))
      (node (ref "U$3") (pin "AT1") (pinfunction "1_AT1") (pintype "bidirectional"))
    )
    (net (code "59") (name "Net-(E12A-B0)") (class "Default")
      (node (ref "E12") (pin "5") (pinfunction "B0_5") (pintype "input"))
      (node (ref "U$3") (pin "BE2") (pinfunction "1_BE2") (pintype "bidirectional"))
    )
    (net (code "60") (name "Net-(E12A-B1)") (class "Default")
      (node (ref "E12") (pin "2") (pinfunction "B1_2") (pintype "input"))
      (node (ref "U$3") (pin "BA1") (pinfunction "1_BA1") (pintype "bidirectional"))
    )
    (net (code "61") (name "Net-(E12A-B2)") (class "Default")
      (node (ref "E12") (pin "22") (pinfunction "B2_22") (pintype "input"))
      (node (ref "E21") (pin "6") (pinfunction "C0_6") (pintype "input"))
      (node (ref "U$3") (pin "AU1") (pinfunction "1_AU1") (pintype "bidirectional"))
    )
    (net (code "62") (name "Net-(E12A-B3)") (class "Default")
      (node (ref "E12") (pin "19") (pinfunction "B3_19") (pintype "input"))
      (node (ref "E21") (pin "3") (pinfunction "C1_3") (pintype "input"))
      (node (ref "U$3") (pin "AS1") (pinfunction "1_AS1") (pintype "bidirectional"))
    )
    (net (code "63") (name "Net-(E12A-C2)") (class "Default")
      (node (ref "E12") (pin "21") (pinfunction "C2_21") (pintype "input"))
      (node (ref "E3") (pin "5") (pinfunction "B0_5") (pintype "input"))
      (node (ref "U$3") (pin "AM2") (pinfunction "1_AM2") (pintype "bidirectional"))
    )
    (net (code "64") (name "Net-(E12A-C3)") (class "Default")
      (node (ref "E12") (pin "18") (pinfunction "C3_18") (pintype "input"))
      (node (ref "E3") (pin "2") (pinfunction "B1_2") (pintype "input"))
      (node (ref "U$3") (pin "AK2") (pinfunction "1_AK2") (pintype "bidirectional"))
    )
    (net (code "65") (name "Net-(E12A-DOT)") (class "Default")
      (node (ref "E12") (pin "15") (pinfunction "DOT_15") (pintype "input"))
      (node (ref "E19") (pin "4") (pinfunction "O_4") (pintype "output"))
      (node (ref "E20") (pin "15") (pinfunction "DOT_15") (pintype "input"))
      (node (ref "E21") (pin "15") (pinfunction "DOT_15") (pintype "input"))
      (node (ref "E3") (pin "15") (pinfunction "DOT_15") (pintype "input"))
      (node (ref "E7") (pin "15") (pinfunction "DOT_15") (pintype "input"))
    )
    (net (code "66") (name "Net-(E12A-F0)") (class "Default")
      (node (ref "E12") (pin "10") (pinfunction "F0_10") (pintype "output"))
      (node (ref "E13") (pin "3") (pinfunction "2D_3") (pintype "input"))
    )
    (net (code "67") (name "Net-(E12A-F1)") (class "Default")
      (node (ref "E12") (pin "11") (pinfunction "F1_11") (pintype "output"))
      (node (ref "E13") (pin "2") (pinfunction "1D_2") (pintype "input"))
    )
    (net (code "68") (name "Net-(E12A-F2)") (class "Default")
      (node (ref "E12") (pin "13") (pinfunction "F2_13") (pintype "output"))
      (node (ref "E8") (pin "11") (pinfunction "10D_11") (pintype "input"))
    )
    (net (code "69") (name "Net-(E12A-F3)") (class "Default")
      (node (ref "E12") (pin "14") (pinfunction "F3_14") (pintype "output"))
      (node (ref "E8") (pin "10") (pinfunction "9D_10") (pintype "input"))
    )
    (net (code "70") (name "Net-(E12A-S0)") (class "Default")
      (node (ref "E12") (pin "17") (pinfunction "S0_17") (pintype "input"))
      (node (ref "E19") (pin "6") (pinfunction "I1_6") (pintype "input"))
      (node (ref "E20") (pin "17") (pinfunction "S0_17") (pintype "input"))
      (node (ref "E21") (pin "17") (pinfunction "S0_17") (pintype "input"))
      (node (ref "E3") (pin "17") (pinfunction "S0_17") (pintype "input"))
      (node (ref "E4") (pin "11") (pinfunction "O_11") (pintype "output"))
      (node (ref "E7") (pin "17") (pinfunction "S0_17") (pintype "input"))
    )
    (net (code "71") (name "Net-(E12A-S1)") (class "Default")
      (node (ref "E12") (pin "16") (pinfunction "S1_16") (pintype "input"))
      (node (ref "E19") (pin "5") (pinfunction "I0_5") (pintype "input"))
      (node (ref "E20") (pin "16") (pinfunction "S1_16") (pintype "input"))
      (node (ref "E21") (pin "16") (pinfunction "S1_16") (pintype "input"))
      (node (ref "E3") (pin "16") (pinfunction "S1_16") (pintype "input"))
      (node (ref "E4") (pin "8") (pinfunction "O_8") (pintype "output"))
      (node (ref "E7") (pin "16") (pinfunction "S1_16") (pintype "input"))
    )
    (net (code "72") (name "Net-(E13A-1Q)") (class "Default")
      (node (ref "E1") (pin "5") (pinfunction "I0_5") (pintype "input"))
      (node (ref "E13") (pin "22") (pinfunction "1Q_22") (pintype "tri_state"))
      (node (ref "E5") (pin "2") (pinfunction "I0_2") (pintype "input"))
      (node (ref "E6") (pin "12") (pinfunction "A1_12") (pintype "input"))
      (node (ref "U$3") (pin "AJ1") (pinfunction "1_AJ1") (pintype "bidirectional"))
    )
    (net (code "73") (name "Net-(E13A-3D)") (class "Default")
      (node (ref "E13") (pin "4") (pinfunction "3D_4") (pintype "input"))
      (node (ref "E20") (pin "14") (pinfunction "F3_14") (pintype "output"))
    )
    (net (code "74") (name "Net-(E13A-4D)") (class "Default")
      (node (ref "E13") (pin "5") (pinfunction "4D_5") (pintype "input"))
      (node (ref "E20") (pin "13") (pinfunction "F2_13") (pintype "output"))
    )
    (net (code "75") (name "Net-(E13A-5D)") (class "Default")
      (node (ref "E13") (pin "6") (pinfunction "5D_6") (pintype "input"))
      (node (ref "E20") (pin "11") (pinfunction "F1_11") (pintype "output"))
    )
    (net (code "76") (name "Net-(E13A-6D)") (class "Default")
      (node (ref "E13") (pin "7") (pinfunction "6D_7") (pintype "input"))
      (node (ref "E20") (pin "10") (pinfunction "F0_10") (pintype "output"))
    )
    (net (code "77") (name "Net-(E13A-7D)") (class "Default")
      (node (ref "E13") (pin "8") (pinfunction "7D_8") (pintype "input"))
      (node (ref "E21") (pin "14") (pinfunction "F3_14") (pintype "output"))
    )
    (net (code "78") (name "Net-(E13A-7Q)") (class "Default")
      (node (ref "E13") (pin "16") (pinfunction "7Q_16") (pintype "tri_state"))
      (node (ref "E15") (pin "2") (pinfunction "I0_2") (pintype "input"))
      (node (ref "E16") (pin "15") (pinfunction "A3_15") (pintype "input"))
      (node (ref "E20") (pin "4") (pinfunction "A0_4") (pintype "input"))
      (node (ref "U$3") (pin "BN2") (pinfunction "1_BN2") (pintype "bidirectional"))
    )
    (net (code "79") (name "Net-(E13A-8D)") (class "Default")
      (node (ref "E13") (pin "9") (pinfunction "8D_9") (pintype "input"))
      (node (ref "E21") (pin "13") (pinfunction "F2_13") (pintype "output"))
    )
    (net (code "80") (name "Net-(E13A-8Q)") (class "Default")
      (node (ref "E13") (pin "15") (pinfunction "8Q_15") (pintype "tri_state"))
      (node (ref "E16") (pin "13") (pinfunction "A2_13") (pintype "input"))
      (node (ref "E18") (pin "11") (pinfunction "I0_11") (pintype "input"))
      (node (ref "E21") (pin "20") (pinfunction "A3_20") (pintype "input"))
      (node (ref "U$3") (pin "BJ1") (pinfunction "1_BJ1") (pintype "bidirectional"))
    )
    (net (code "81") (name "Net-(E13A-9D)") (class "Default")
      (node (ref "E13") (pin "10") (pinfunction "9D_10") (pintype "input"))
      (node (ref "E21") (pin "11") (pinfunction "F1_11") (pintype "output"))
    )
    (net (code "82") (name "Net-(E13A-9Q)") (class "Default")
      (node (ref "E13") (pin "14") (pinfunction "9Q_14") (pintype "tri_state"))
      (node (ref "E16") (pin "12") (pinfunction "A1_12") (pintype "input"))
      (node (ref "E18") (pin "2") (pinfunction "I0_2") (pintype "input"))
      (node (ref "E21") (pin "23") (pinfunction "A2_23") (pintype "input"))
      (node (ref "U$3") (pin "BL1") (pinfunction "1_BL1") (pintype "bidirectional"))
    )
    (net (code "83") (name "Net-(E13A-10D)") (class "Default")
      (node (ref "E13") (pin "11") (pinfunction "10D_11") (pintype "input"))
      (node (ref "E21") (pin "10") (pinfunction "F0_10") (pintype "output"))
    )
    (net (code "84") (name "Net-(E13A-10Q)") (class "Default")
      (node (ref "E13") (pin "13") (pinfunction "10Q_13") (pintype "tri_state"))
      (node (ref "E15") (pin "11") (pinfunction "I0_11") (pintype "input"))
      (node (ref "E16") (pin "10") (pinfunction "A0_10") (pintype "input"))
      (node (ref "E21") (pin "1") (pinfunction "A1_1") (pintype "input"))
      (node (ref "U$3") (pin "BM1") (pinfunction "1_BM1") (pintype "bidirectional"))
    )
    (net (code "85") (name "Net-(E13A-CLK)") (class "Default")
      (node (ref "E13") (pin "1") (pinfunction "CLK_1") (pintype "input"))
      (node (ref "E4") (pin "3") (pinfunction "O_3") (pintype "output"))
    )
    (net (code "86") (name "Net-(E14A-I0)") (class "Default")
      (node (ref "E14") (pin "2") (pinfunction "I0_2") (pintype "input"))
      (node (ref "U$3") (pin "BC1") (pinfunction "1_BC1") (pintype "bidirectional"))
    )
    (net (code "87") (name "Net-(E14A-I1)") (class "Default")
      (node (ref "E14") (pin "3") (pinfunction "I1_3") (pintype "input"))
      (node (ref "E14") (pin "5") (pinfunction "I0_5") (pintype "input"))
      (node (ref "E19") (pin "8") (pinfunction "I0_8") (pintype "input"))
      (node (ref "E2") (pin "1") (pinfunction "I0_1") (pintype "input"))
      (node (ref "E2") (pin "8") (pinfunction "O_8") (pintype "output"))
    )
    (net (code "88") (name "Net-(E14A-O)") (class "Default")
      (node (ref "E14") (pin "1") (pinfunction "O_1") (pintype "output"))
      (node (ref "E17") (pin "1") (pinfunction "I0_1") (pintype "input"))
      (node (ref "E17") (pin "13") (pinfunction "I1_13") (pintype "input"))
    )
    (net (code "89") (name "Net-(E14B-I1)") (class "Default")
      (node (ref "E14") (pin "6") (pinfunction "I1_6") (pintype "input"))
      (node (ref "U$3") (pin "BD1") (pinfunction "1_BD1") (pintype "bidirectional"))
    )
    (net (code "90") (name "Net-(E14B-O)") (class "Default")
      (node (ref "E14") (pin "4") (pinfunction "O_4") (pintype "output"))
      (node (ref "E17") (pin "10") (pinfunction "I1_10") (pintype "input"))
      (node (ref "E17") (pin "5") (pinfunction "I1_5") (pintype "input"))
    )
    (net (code "91") (name "Net-(E14C-I0)") (class "Default")
      (node (ref "E14") (pin "8") (pinfunction "I0_8") (pintype "input"))
      (node (ref "U$3") (pin "BS2") (pinfunction "1_BS2") (pintype "bidirectional"))
    )
    (net (code "92") (name "Net-(E14C-I1)") (class "Default")
      (node (ref "E1") (pin "10") (pinfunction "O_10") (pintype "output"))
      (node (ref "E14") (pin "9") (pinfunction "I1_9") (pintype "input"))
    )
    (net (code "93") (name "Net-(E14D-I0)") (class "Default")
      (node (ref "E1") (pin "2") (pinfunction "I0_2") (pintype "input"))
      (node (ref "E1") (pin "3") (pinfunction "I1_3") (pintype "input"))
      (node (ref "E1") (pin "4") (pinfunction "O_4") (pintype "output"))
      (node (ref "E14") (pin "11") (pinfunction "I0_11") (pintype "input"))
    )
    (net (code "94") (name "Net-(E15A-O)") (class "Default")
      (node (ref "E15") (pin "1") (pinfunction "O_1") (pintype "open_collector"))
      (node (ref "E15") (pin "4") (pinfunction "O_4") (pintype "open_collector"))
      (node (ref "R11") (pin "1") (pinfunction "1_1") (pintype "passive"))
      (node (ref "U$3") (pin "BT1") (pinfunction "1_BT1") (pintype "bidirectional"))
    )
    (net (code "95") (name "Net-(E15B-I0)") (class "Default")
      (node (ref "E15") (pin "5") (pinfunction "I0_5") (pintype "input"))
      (node (ref "E16") (pin "1") (pinfunction "B3_1") (pintype "input"))
      (node (ref "E7") (pin "23") (pinfunction "A2_23") (pintype "input"))
      (node (ref "E8") (pin "16") (pinfunction "7Q_16") (pintype "tri_state"))
      (node (ref "U$3") (pin "AR2") (pinfunction "1_AR2") (pintype "bidirectional"))
    )
    (net (code "96") (name "Net-(E15C-O)") (class "Default")
      (node (ref "E15") (pin "10") (pinfunction "O_10") (pintype "open_collector"))
      (node (ref "E15") (pin "13") (pinfunction "O_13") (pintype "open_collector"))
      (node (ref "R14") (pin "1") (pinfunction "1_1") (pintype "passive"))
      (node (ref "U$3") (pin "BU1") (pinfunction "1_BU1") (pintype "bidirectional"))
    )
    (net (code "97") (name "Net-(E16A-B1)") (class "Default")
      (node (ref "E16") (pin "11") (pinfunction "B1_11") (pintype "input"))
      (node (ref "E18") (pin "6") (pinfunction "I1_6") (pintype "input"))
      (node (ref "E7") (pin "4") (pinfunction "A0_4") (pintype "input"))
      (node (ref "E8") (pin "14") (pinfunction "9Q_14") (pintype "tri_state"))
      (node (ref "U$3") (pin "AU2") (pinfunction "1_AU2") (pintype "bidirectional"))
    )
    (net (code "98") (name "Net-(E16A-B2)") (class "Default")
      (node (ref "E16") (pin "14") (pinfunction "B2_14") (pintype "input"))
      (node (ref "E18") (pin "8") (pinfunction "I0_8") (pintype "input"))
      (node (ref "E7") (pin "1") (pinfunction "A1_1") (pintype "input"))
      (node (ref "E8") (pin "15") (pinfunction "8Q_15") (pintype "tri_state"))
      (node (ref "U$3") (pin "AS2") (pinfunction "1_AS2") (pintype "bidirectional"))
    )
    (net (code "99") (name "Net-(E17A-I1)") (class "Default")
      (node (ref "E17") (pin "2") (pinfunction "I1_2") (pintype "input"))
      (node (ref "E17") (pin "4") (pinfunction "I0_4") (pintype "input"))
      (node (ref "U$3") (pin "BF1") (pinfunction "1_BF1") (pintype "bidirectional"))
    )
    (net (code "100") (name "Net-(E17A-O)") (class "Default")
      (node (ref "E17") (pin "3") (pinfunction "O_3") (pintype "output"))
      (node (ref "E22") (pin "1") (pinfunction "I0_1") (pintype "input"))
    )
    (net (code "101") (name "Net-(E17B-O)") (class "Default")
      (node (ref "E17") (pin "6") (pinfunction "O_6") (pintype "output"))
      (node (ref "E22") (pin "4") (pinfunction "I0_4") (pintype "input"))
    )
    (net (code "102") (name "Net-(E17C-I0)") (class "Default")
      (node (ref "E17") (pin "12") (pinfunction "I0_12") (pintype "input"))
      (node (ref "E17") (pin "9") (pinfunction "I0_9") (pintype "input"))
      (node (ref "U$3") (pin "BE1") (pinfunction "1_BE1") (pintype "bidirectional"))
    )
    (net (code "103") (name "Net-(E17C-O)") (class "Default")
      (node (ref "E17") (pin "8") (pinfunction "O_8") (pintype "output"))
      (node (ref "E4") (pin "1") (pinfunction "I0_1") (pintype "input"))
    )
    (net (code "104") (name "Net-(E17D-O)") (class "Default")
      (node (ref "E17") (pin "11") (pinfunction "O_11") (pintype "output"))
      (node (ref "E4") (pin "4") (pinfunction "I0_4") (pintype "input"))
    )
    (net (code "105") (name "Net-(E18A-O)") (class "Default")
      (node (ref "E18") (pin "1") (pinfunction "O_1") (pintype "open_collector"))
      (node (ref "E18") (pin "4") (pinfunction "O_4") (pintype "open_collector"))
      (node (ref "R13") (pin "1") (pinfunction "1_1") (pintype "passive"))
      (node (ref "U$3") (pin "BU2") (pinfunction "1_BU2") (pintype "bidirectional"))
    )
    (net (code "106") (name "Net-(E18C-O)") (class "Default")
      (node (ref "E18") (pin "10") (pinfunction "O_10") (pintype "open_collector"))
      (node (ref "E18") (pin "13") (pinfunction "O_13") (pintype "open_collector"))
      (node (ref "R12") (pin "1") (pinfunction "1_1") (pintype "passive"))
      (node (ref "U$3") (pin "BT2") (pinfunction "1_BT2") (pintype "bidirectional"))
    )
    (net (code "107") (name "Net-(E19A-I0)") (class "Default")
      (node (ref "E19") (pin "2") (pinfunction "I0_2") (pintype "input"))
      (node (ref "E19") (pin "3") (pinfunction "I1_3") (pintype "input"))
      (node (ref "E22") (pin "13") (pinfunction "I1_13") (pintype "input"))
      (node (ref "E6") (pin "7") (pinfunction "A<B_O_7") (pintype "output"))
      (node (ref "U$3") (pin "BR2") (pinfunction "1_BR2") (pintype "bidirectional"))
    )
    (net (code "108") (name "Net-(E19A-O)") (class "Default")
      (node (ref "E19") (pin "1") (pinfunction "O_1") (pintype "output"))
      (node (ref "E22") (pin "10") (pinfunction "I1_10") (pintype "input"))
    )
    (net (code "109") (name "Net-(E19C-I1)") (class "Default")
      (node (ref "E19") (pin "9") (pinfunction "I1_9") (pintype "input"))
      (node (ref "U$3") (pin "BS1") (pinfunction "1_BS1") (pintype "bidirectional"))
    )
    (net (code "110") (name "Net-(E19C-O)") (class "Default")
      (node (ref "E19") (pin "10") (pinfunction "O_10") (pintype "output"))
      (node (ref "E19") (pin "11") (pinfunction "I0_11") (pintype "input"))
      (node (ref "E22") (pin "12") (pinfunction "I0_12") (pintype "input"))
      (node (ref "E22") (pin "9") (pinfunction "I0_9") (pintype "input"))
    )
    (net (code "111") (name "Net-(E19D-I1)") (class "Default")
      (node (ref "E19") (pin "12") (pinfunction "I1_12") (pintype "input"))
      (node (ref "E23") (pin "8") (pinfunction "Q_8") (pintype "output"))
    )
    (net (code "112") (name "Net-(E20A-B0)") (class "Default")
      (node (ref "E20") (pin "5") (pinfunction "B0_5") (pintype "input"))
      (node (ref "U$3") (pin "BP2") (pinfunction "1_BP2") (pintype "bidirectional"))
    )
    (net (code "113") (name "Net-(E20A-B1)") (class "Default")
      (node (ref "E20") (pin "2") (pinfunction "B1_2") (pintype "input"))
      (node (ref "U$3") (pin "BM2") (pinfunction "1_BM2") (pintype "bidirectional"))
    )
    (net (code "114") (name "Net-(E20A-B2)") (class "Default")
      (node (ref "E20") (pin "22") (pinfunction "B2_22") (pintype "input"))
      (node (ref "U$3") (pin "BJ2") (pinfunction "1_BJ2") (pintype "bidirectional"))
    )
    (net (code "115") (name "Net-(E20A-B3)") (class "Default")
      (node (ref "E20") (pin "19") (pinfunction "B3_19") (pintype "input"))
      (node (ref "U$3") (pin "BF2") (pinfunction "1_BF2") (pintype "bidirectional"))
    )
    (net (code "116") (name "Net-(E20A-C0)") (class "Default")
      (node (ref "E20") (pin "6") (pinfunction "C0_6") (pintype "input"))
      (node (ref "E7") (pin "22") (pinfunction "B2_22") (pintype "input"))
      (node (ref "U$3") (pin "AP2") (pinfunction "1_AP2") (pintype "bidirectional"))
    )
    (net (code "117") (name "Net-(E21A-B0)") (class "Default")
      (node (ref "E21") (pin "5") (pinfunction "B0_5") (pintype "input"))
      (node (ref "U$3") (pin "BP1") (pinfunction "1_BP1") (pintype "bidirectional"))
    )
    (net (code "118") (name "Net-(E21A-B1)") (class "Default")
      (node (ref "E21") (pin "2") (pinfunction "B1_2") (pintype "input"))
      (node (ref "U$3") (pin "BN1") (pinfunction "1_BN1") (pintype "bidirectional"))
    )
    (net (code "119") (name "Net-(E21A-B2)") (class "Default")
      (node (ref "E21") (pin "22") (pinfunction "B2_22") (pintype "input"))
      (node (ref "U$3") (pin "BK1") (pinfunction "1_BK1") (pintype "bidirectional"))
    )
    (net (code "120") (name "Net-(E21A-B3)") (class "Default")
      (node (ref "E21") (pin "19") (pinfunction "B3_19") (pintype "input"))
      (node (ref "U$3") (pin "BH1") (pinfunction "1_BH1") (pintype "bidirectional"))
    )
    (net (code "121") (name "Net-(E21A-C2)") (class "Default")
      (node (ref "E21") (pin "21") (pinfunction "C2_21") (pintype "input"))
      (node (ref "E7") (pin "5") (pinfunction "B0_5") (pintype "input"))
      (node (ref "U$3") (pin "AV2") (pinfunction "1_AV2") (pintype "bidirectional"))
    )
    (net (code "122") (name "Net-(E21A-C3)") (class "Default")
      (node (ref "E21") (pin "18") (pinfunction "C3_18") (pintype "input"))
      (node (ref "E7") (pin "2") (pinfunction "B1_2") (pintype "input"))
      (node (ref "U$3") (pin "AT2") (pinfunction "1_AT2") (pintype "bidirectional"))
    )
    (net (code "123") (name "Net-(E22A-I1)") (class "Default")
      (node (ref "E22") (pin "11") (pinfunction "O_11") (pintype "output"))
      (node (ref "E22") (pin "2") (pinfunction "I1_2") (pintype "input"))
    )
    (net (code "124") (name "Net-(E22B-I1)") (class "Default")
      (node (ref "E22") (pin "5") (pinfunction "I1_5") (pintype "input"))
      (node (ref "E22") (pin "8") (pinfunction "O_8") (pintype "output"))
    )
    (net (code "125") (name "Net-(E23A-P$5)") (class "Default")
      (node (ref "C27") (pin "2") (pinfunction "2_2") (pintype "passive"))
      (node (ref "E23") (pin "11") (pinfunction "P$5_11") (pintype "bidirectional"))
    )
    (net (code "126") (name "Net-(E23A-P$6)") (class "Default")
      (node (ref "C27") (pin "1") (pinfunction "1_1") (pintype "passive"))
      (node (ref "E23") (pin "13") (pinfunction "P$6_13") (pintype "bidirectional"))
      (node (ref "R15") (pin "1") (pinfunction "1_1") (pintype "passive"))
    )
    (net (code "127") (name "VCC") (class "Default")
      (node (ref "C1") (pin "1") (pinfunction "1_1") (pintype "passive"))
      (node (ref "C10") (pin "1") (pinfunction "1_1") (pintype "passive"))
      (node (ref "C11") (pin "1") (pinfunction "1_1") (pintype "passive"))
      (node (ref "C12") (pin "1") (pinfunction "1_1") (pintype "passive"))
      (node (ref "C13") (pin "1") (pinfunction "1_1") (pintype "passive"))
      (node (ref "C14") (pin "1") (pinfunction "1_1") (pintype "passive"))
      (node (ref "C15") (pin "1") (pinfunction "1_1") (pintype "passive"))
      (node (ref "C16") (pin "1") (pinfunction "1_1") (pintype "passive"))
      (node (ref "C17") (pin "1") (pinfunction "1_1") (pintype "passive"))
      (node (ref "C18") (pin "1") (pinfunction "1_1") (pintype "passive"))
      (node (ref "C19") (pin "1") (pinfunction "1_1") (pintype "passive"))
      (node (ref "C2") (pin "1") (pinfunction "1_1") (pintype "passive"))
      (node (ref "C20") (pin "1") (pinfunction "1_1") (pintype "passive"))
      (node (ref "C21") (pin "1") (pinfunction "1_1") (pintype "passive"))
      (node (ref "C22") (pin "1") (pinfunction "1_1") (pintype "passive"))
      (node (ref "C23") (pin "1") (pinfunction "1_1") (pintype "passive"))
      (node (ref "C24") (pin "+") (pinfunction "+_+") (pintype "passive"))
      (node (ref "C25") (pin "+") (pinfunction "+_+") (pintype "passive"))
      (node (ref "C3") (pin "1") (pinfunction "1_1") (pintype "passive"))
      (node (ref "C4") (pin "1") (pinfunction "1_1") (pintype "passive"))
      (node (ref "C5") (pin "1") (pinfunction "1_1") (pintype "passive"))
      (node (ref "C6") (pin "1") (pinfunction "1_1") (pintype "passive"))
      (node (ref "C7") (pin "1") (pinfunction "1_1") (pintype "passive"))
      (node (ref "C8") (pin "1") (pinfunction "1_1") (pintype "passive"))
      (node (ref "C9") (pin "1") (pinfunction "1_1") (pintype "passive"))
      (node (ref "R1") (pin "2") (pinfunction "2_2") (pintype "passive"))
      (node (ref "R10") (pin "2") (pinfunction "2_2") (pintype "passive"))
      (node (ref "R11") (pin "2") (pinfunction "2_2") (pintype "passive"))
      (node (ref "R12") (pin "2") (pinfunction "2_2") (pintype "passive"))
      (node (ref "R13") (pin "2") (pinfunction "2_2") (pintype "passive"))
      (node (ref "R14") (pin "2") (pinfunction "2_2") (pintype "passive"))
      (node (ref "R15") (pin "2") (pinfunction "2_2") (pintype "passive"))
      (node (ref "R3") (pin "2") (pinfunction "2_2") (pintype "passive"))
      (node (ref "R5") (pin "2") (pinfunction "2_2") (pintype "passive"))
      (node (ref "R6") (pin "2") (pinfunction "2_2") (pintype "passive"))
      (node (ref "R7") (pin "2") (pinfunction "2_2") (pintype "passive"))
      (node (ref "R8") (pin "2") (pinfunction "2_2") (pintype "passive"))
      (node (ref "R9") (pin "2") (pinfunction "2_2") (pintype "passive"))
      (node (ref "U$3") (pin "AA2") (pinfunction "1_AA2") (pintype "bidirectional"))
      (node (ref "U$3") (pin "BA2") (pinfunction "1_BA2") (pintype "bidirectional"))
    )
    (net (code "128") (name "unconnected-(DL1-5-Pad2)") (class "Default")
      (node (ref "DL1") (pin "2") (pinfunction "5_2") (pintype "passive"))
    )
    (net (code "129") (name "unconnected-(DL1-15-Pad4)") (class "Default")
      (node (ref "DL1") (pin "4") (pinfunction "15_4") (pintype "passive"))
    )
    (net (code "130") (name "unconnected-(DL1-25-Pad6)") (class "Default")
      (node (ref "DL1") (pin "6") (pinfunction "25_6") (pintype "passive"))
    )
    (net (code "131") (name "unconnected-(DL1-30-Pad7)") (class "Default")
      (node (ref "DL1") (pin "7") (pinfunction "30_7") (pintype "passive"))
    )
    (net (code "132") (name "unconnected-(DL1-35-Pad8)") (class "Default")
      (node (ref "DL1") (pin "8") (pinfunction "35_8") (pintype "passive"))
    )
    (net (code "133") (name "unconnected-(DL1-40-Pad9)") (class "Default")
      (node (ref "DL1") (pin "9") (pinfunction "40_9") (pintype "passive"))
    )
    (net (code "134") (name "unconnected-(DL1-45-Pad10)") (class "Default")
      (node (ref "DL1") (pin "10") (pinfunction "45_10") (pintype "passive"))
    )
    (net (code "135") (name "unconnected-(E3A-G0-Pad7)") (class "Default")
      (node (ref "E3") (pin "7") (pinfunction "G0_7") (pintype "input"))
    )
    (net (code "136") (name "unconnected-(E3A-G1-Pad8)") (class "Default")
      (node (ref "E3") (pin "8") (pinfunction "G1_8") (pintype "input"))
    )
    (net (code "137") (name "unconnected-(E3A-G2-Pad9)") (class "Default")
      (node (ref "E3") (pin "9") (pinfunction "G2_9") (pintype "input"))
    )
    (net (code "138") (name "unconnected-(E6A-A>B_O-Pad5)") (class "Default")
      (node (ref "E6") (pin "5") (pinfunction "A>B_O_5") (pintype "output"))
    )
    (net (code "139") (name "unconnected-(E7A-G0-Pad7)") (class "Default")
      (node (ref "E7") (pin "7") (pinfunction "G0_7") (pintype "input"))
    )
    (net (code "140") (name "unconnected-(E7A-G1-Pad8)") (class "Default")
      (node (ref "E7") (pin "8") (pinfunction "G1_8") (pintype "input"))
    )
    (net (code "141") (name "unconnected-(E7A-G2-Pad9)") (class "Default")
      (node (ref "E7") (pin "9") (pinfunction "G2_9") (pintype "input"))
    )
    (net (code "142") (name "unconnected-(E12A-G0-Pad7)") (class "Default")
      (node (ref "E12") (pin "7") (pinfunction "G0_7") (pintype "input"))
    )
    (net (code "143") (name "unconnected-(E12A-G1-Pad8)") (class "Default")
      (node (ref "E12") (pin "8") (pinfunction "G1_8") (pintype "input"))
    )
    (net (code "144") (name "unconnected-(E12A-G2-Pad9)") (class "Default")
      (node (ref "E12") (pin "9") (pinfunction "G2_9") (pintype "input"))
    )
    (net (code "145") (name "unconnected-(E20A-G0-Pad7)") (class "Default")
      (node (ref "E20") (pin "7") (pinfunction "G0_7") (pintype "input"))
    )
    (net (code "146") (name "unconnected-(E20A-G1-Pad8)") (class "Default")
      (node (ref "E20") (pin "8") (pinfunction "G1_8") (pintype "input"))
    )
    (net (code "147") (name "unconnected-(E20A-G2-Pad9)") (class "Default")
      (node (ref "E20") (pin "9") (pinfunction "G2_9") (pintype "input"))
    )
    (net (code "148") (name "unconnected-(E21A-G0-Pad7)") (class "Default")
      (node (ref "E21") (pin "7") (pinfunction "G0_7") (pintype "input"))
    )
    (net (code "149") (name "unconnected-(E21A-G1-Pad8)") (class "Default")
      (node (ref "E21") (pin "8") (pinfunction "G1_8") (pintype "input"))
    )
    (net (code "150") (name "unconnected-(E21A-G2-Pad9)") (class "Default")
      (node (ref "E21") (pin "9") (pinfunction "G2_9") (pintype "input"))
    )
    (net (code "151") (name "unconnected-(E23A-~{Q}-Pad6)") (class "Default")
      (node (ref "E23") (pin "6") (pinfunction "~{Q}_6") (pintype "output"))
    )
  )
)
